# source_eagle.net
KiCad netlist of a schematic drawn in EAGLE
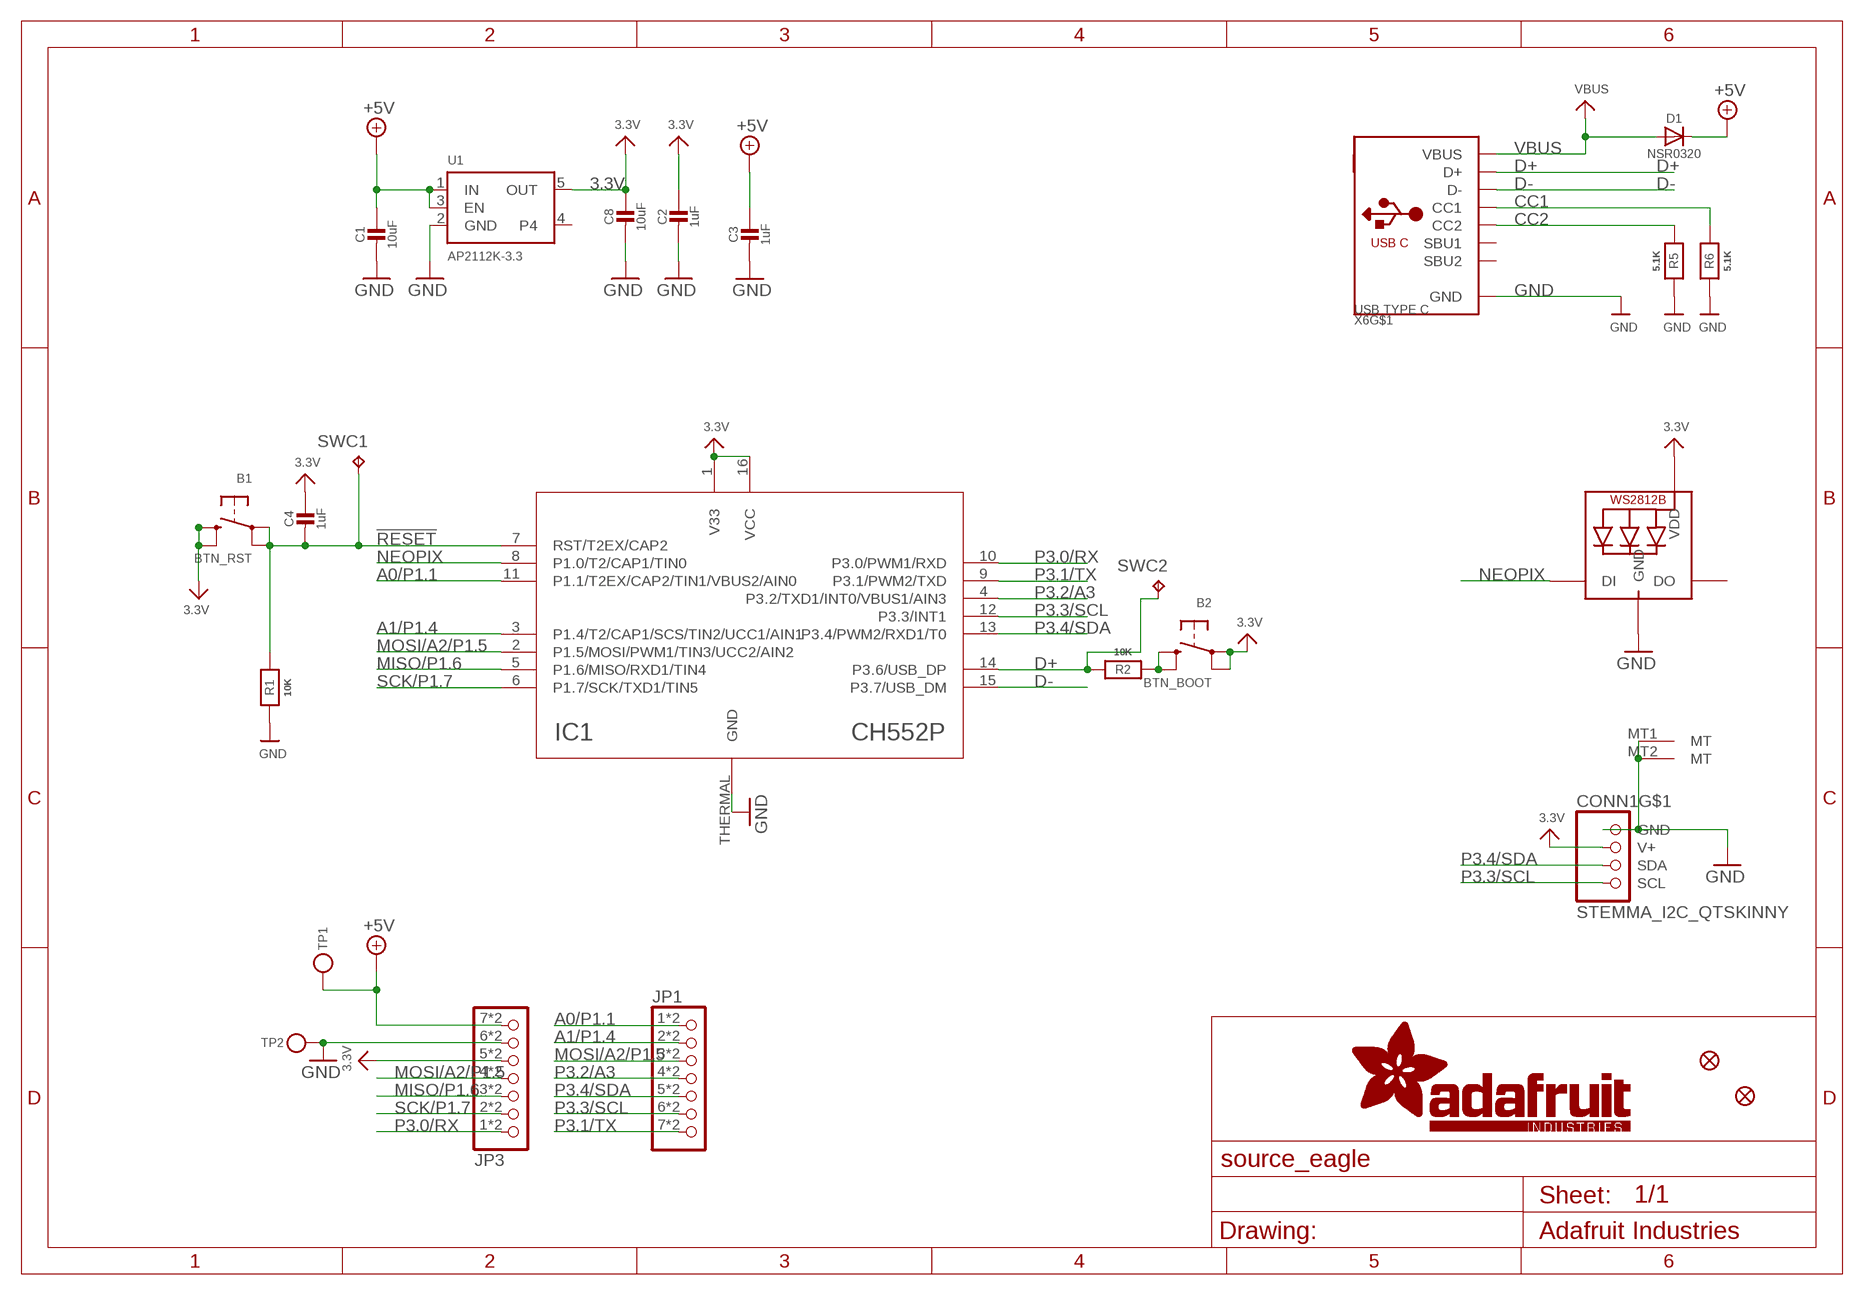
[diagram p0: schematic, sheet 1]

(export (version "E")
  (design (tool "Eeschema 10.0.6"))
  (components
    (comp (ref "B1")
      (value "BTN_RST")
      (footprint "eagle-import:BTN_RKB2_4.6X2.8")
      (libsource (lib "eagle-import") (part "SWITCH_TACT_SMT_RKB2"))
    )
    (comp (ref "B2")
      (value "BTN_BOOT")
      (footprint "eagle-import:BTN_RKB2_4.6X2.8")
      (libsource (lib "eagle-import") (part "SWITCH_TACT_SMT_RKB2"))
    )
    (comp (ref "C1")
      (value "10uF")
      (footprint "eagle-import:_0805MP")
      (libsource (lib "eagle-import") (part "CAP_CERAMIC_0805MP"))
    )
    (comp (ref "C2")
      (value "1uF")
      (footprint "eagle-import:_0402NO")
      (libsource (lib "eagle-import") (part "CAP_CERAMIC_0402NO"))
    )
    (comp (ref "C3")
      (value "1uF")
      (footprint "eagle-import:_0402NO")
      (libsource (lib "eagle-import") (part "CAP_CERAMIC_0402NO"))
    )
    (comp (ref "C4")
      (value "1uF")
      (footprint "eagle-import:_0402NO")
      (libsource (lib "eagle-import") (part "CAP_CERAMIC_0402NO"))
    )
    (comp (ref "C8")
      (value "10uF")
      (footprint "eagle-import:_0805MP")
      (libsource (lib "eagle-import") (part "CAP_CERAMIC_0805MP"))
    )
    (comp (ref "CONN1")
      (value "STEMMA_I2C_QTSKINNY")
      (footprint "eagle-import:JST_SH4_SKINNY")
      (libsource (lib "eagle-import") (part "STEMMA_I2C_QTSKINNY"))
    )
    (comp (ref "D1")
      (value "NSR0320")
      (footprint "eagle-import:SOD-323_MINI")
      (libsource (lib "eagle-import") (part "DIODE_SOD323MINI"))
    )
    (comp (ref "IC1")
      (value "CH552PP")
      (footprint "eagle-import:QFN16_3MM")
      (libsource (lib "eagle-import") (part "CH552PP"))
    )
    (comp (ref "JP1")
      (value "HEADER-1X7_CASTEL")
      (footprint "eagle-import:1X07_CASTEL")
      (libsource (lib "eagle-import") (part "HEADER-1X7_CASTEL"))
    )
    (comp (ref "JP3")
      (value "HEADER-1X7_CASTEL")
      (footprint "eagle-import:1X07_CASTEL")
      (libsource (lib "eagle-import") (part "HEADER-1X7_CASTEL"))
    )
    (comp (ref "LED1")
      (value "WS2812B_SK6805_1515")
      (footprint "eagle-import:SK6805_1515")
      (libsource (lib "eagle-import") (part "WS2812B_SK6805_1515"))
    )
    (comp (ref "R1")
      (value "10K")
      (footprint "eagle-import:_0402NO")
      (libsource (lib "eagle-import") (part "RESISTOR_0402NO"))
    )
    (comp (ref "R2")
      (value "10K")
      (footprint "eagle-import:_0402NO")
      (libsource (lib "eagle-import") (part "RESISTOR_0402NO"))
    )
    (comp (ref "R5")
      (value "5.1K")
      (footprint "eagle-import:_0402NO")
      (libsource (lib "eagle-import") (part "RESISTOR_0402NO"))
    )
    (comp (ref "R6")
      (value "5.1K")
      (footprint "eagle-import:_0402NO")
      (libsource (lib "eagle-import") (part "RESISTOR_0402NO"))
    )
    (comp (ref "SWC1")
      (value "TPB1,27")
      (footprint "eagle-import:B1,27")
      (libsource (lib "eagle-import") (part "TPB1,27"))
    )
    (comp (ref "SWC2")
      (value "TPTP15R")
      (footprint "eagle-import:TP15R")
      (libsource (lib "eagle-import") (part "TPTP15R"))
    )
    (comp (ref "TP1")
      (value "TESTPOINT_PLUS13")
      (footprint "eagle-import:TESTPOINT_PLUS_1X3MM")
      (libsource (lib "eagle-import") (part "TESTPOINT_PLUS13"))
    )
    (comp (ref "TP2")
      (value "TESTPOINT_MINUS")
      (footprint "eagle-import:TESTPOINT_MINUS_1X3MM")
      (libsource (lib "eagle-import") (part "TESTPOINT_MINUS"))
    )
    (comp (ref "U$6")
      (value "FIDUCIAL_1MM")
      (footprint "eagle-import:FIDUCIAL_1MM")
      (libsource (lib "eagle-import") (part "FIDUCIAL_1MM"))
    )
    (comp (ref "U$8")
      (value "FIDUCIAL_1MM")
      (footprint "eagle-import:FIDUCIAL_1MM")
      (libsource (lib "eagle-import") (part "FIDUCIAL_1MM"))
    )
    (comp (ref "U1")
      (value "AP2112K-3.3")
      (footprint "eagle-import:SOT23-5")
      (libsource (lib "eagle-import") (part "VREG_SOT23-5"))
    )
    (comp (ref "X6")
      (value "USB TYPE C")
      (footprint "eagle-import:USB_C_CUSB31-CFM2AX-01-X")
      (libsource (lib "eagle-import") (part "USB_C"))
    )
  )
  (nets
    (net (code "1") (name "+5V") (class "Default")
      (node (ref "C1") (pin "1") (pinfunction "1_1") (pintype "passive"))
      (node (ref "C3") (pin "1") (pinfunction "1_1") (pintype "passive"))
      (node (ref "D1") (pin "C") (pinfunction "C_C") (pintype "passive"))
      (node (ref "JP3") (pin "7") (pinfunction "7_7") (pintype "passive"))
      (node (ref "JP3") (pin "7C") (pinfunction "7_7C") (pintype "passive"))
      (node (ref "TP1") (pin "P$1") (pinfunction "P$1_P$1") (pintype "bidirectional"))
      (node (ref "U1") (pin "1") (pinfunction "IN_1") (pintype "power_in"))
      (node (ref "U1") (pin "3") (pinfunction "EN_3") (pintype "input"))
    )
    (net (code "2") (name "/A0{slash}P1.1") (class "Default")
      (node (ref "IC1") (pin "11") (pinfunction "P1.1/T2EX/CAP2/TIN1/VBUS2/AIN0_11") (pintype "bidirectional"))
      (node (ref "JP1") (pin "1") (pinfunction "1_1") (pintype "passive"))
      (node (ref "JP1") (pin "1C") (pinfunction "1_1C") (pintype "passive"))
    )
    (net (code "3") (name "/A1{slash}P1.4") (class "Default")
      (node (ref "IC1") (pin "3") (pinfunction "P1.4/T2/CAP1/SCS/TIN2/UCC1/AIN1_3") (pintype "bidirectional"))
      (node (ref "JP1") (pin "2") (pinfunction "2_2") (pintype "passive"))
      (node (ref "JP1") (pin "2C") (pinfunction "2_2C") (pintype "passive"))
    )
    (net (code "4") (name "/CC1") (class "Default")
      (node (ref "R6") (pin "2") (pinfunction "2_2") (pintype "passive"))
      (node (ref "X6") (pin "A5") (pinfunction "CC1_A5") (pintype "bidirectional"))
    )
    (net (code "5") (name "/CC2") (class "Default")
      (node (ref "R5") (pin "2") (pinfunction "2_2") (pintype "passive"))
      (node (ref "X6") (pin "B5") (pinfunction "CC2_B5") (pintype "bidirectional"))
    )
    (net (code "6") (name "/D+") (class "Default")
      (node (ref "IC1") (pin "14") (pinfunction "P3.6/USB_DP_14") (pintype "bidirectional"))
      (node (ref "R2") (pin "2") (pinfunction "2_2") (pintype "passive"))
      (node (ref "SWC2") (pin "TP") (pinfunction "TP_TP") (pintype "input"))
      (node (ref "X6") (pin "A6") (pinfunction "D+_A6") (pintype "bidirectional"))
      (node (ref "X6") (pin "B6") (pinfunction "D+_B6") (pintype "bidirectional"))
    )
    (net (code "7") (name "/D-") (class "Default")
      (node (ref "IC1") (pin "15") (pinfunction "P3.7/USB_DM_15") (pintype "bidirectional"))
      (node (ref "X6") (pin "A7") (pinfunction "D-_A7") (pintype "bidirectional"))
      (node (ref "X6") (pin "B7") (pinfunction "D-_B7") (pintype "bidirectional"))
    )
    (net (code "8") (name "/MISO{slash}P1.6") (class "Default")
      (node (ref "IC1") (pin "5") (pinfunction "P1.6/MISO/RXD1/TIN4_5") (pintype "bidirectional"))
      (node (ref "JP3") (pin "3") (pinfunction "3_3") (pintype "passive"))
      (node (ref "JP3") (pin "3C") (pinfunction "3_3C") (pintype "passive"))
    )
    (net (code "9") (name "/MOSI{slash}A2{slash}P1.5") (class "Default")
      (node (ref "IC1") (pin "2") (pinfunction "P1.5/MOSI/PWM1/TIN3/UCC2/AIN2_2") (pintype "bidirectional"))
      (node (ref "JP1") (pin "3") (pinfunction "3_3") (pintype "passive"))
      (node (ref "JP1") (pin "3C") (pinfunction "3_3C") (pintype "passive"))
      (node (ref "JP3") (pin "4") (pinfunction "4_4") (pintype "passive"))
      (node (ref "JP3") (pin "4C") (pinfunction "4_4C") (pintype "passive"))
    )
    (net (code "10") (name "/NEOPIX") (class "Default")
      (node (ref "IC1") (pin "8") (pinfunction "P1.0/T2/CAP1/TIN0_8") (pintype "bidirectional"))
      (node (ref "LED1") (pin "1") (pinfunction "DI_1") (pintype "input"))
    )
    (net (code "11") (name "/P3.0{slash}RX") (class "Default")
      (node (ref "IC1") (pin "10") (pinfunction "P3.0/PWM1/RXD_10") (pintype "bidirectional"))
      (node (ref "JP3") (pin "1") (pinfunction "1_1") (pintype "passive"))
      (node (ref "JP3") (pin "1C") (pinfunction "1_1C") (pintype "passive"))
    )
    (net (code "12") (name "/P3.1{slash}TX") (class "Default")
      (node (ref "IC1") (pin "9") (pinfunction "P3.1/PWM2/TXD_9") (pintype "bidirectional"))
      (node (ref "JP1") (pin "7") (pinfunction "7_7") (pintype "passive"))
      (node (ref "JP1") (pin "7C") (pinfunction "7_7C") (pintype "passive"))
    )
    (net (code "13") (name "/P3.2{slash}A3") (class "Default")
      (node (ref "IC1") (pin "4") (pinfunction "P3.2/TXD1/INT0/VBUS1/AIN3_4") (pintype "bidirectional"))
      (node (ref "JP1") (pin "4") (pinfunction "4_4") (pintype "passive"))
      (node (ref "JP1") (pin "4C") (pinfunction "4_4C") (pintype "passive"))
    )
    (net (code "14") (name "/P3.3{slash}SCL") (class "Default")
      (node (ref "CONN1") (pin "4") (pinfunction "SCL_4") (pintype "passive"))
      (node (ref "IC1") (pin "12") (pinfunction "P3.3/INT1_12") (pintype "bidirectional"))
      (node (ref "JP1") (pin "6") (pinfunction "6_6") (pintype "passive"))
      (node (ref "JP1") (pin "6C") (pinfunction "6_6C") (pintype "passive"))
    )
    (net (code "15") (name "/P3.4{slash}SDA") (class "Default")
      (node (ref "CONN1") (pin "3") (pinfunction "SDA_3") (pintype "passive"))
      (node (ref "IC1") (pin "13") (pinfunction "P3.4/PWM2/RXD1/T0_13") (pintype "bidirectional"))
      (node (ref "JP1") (pin "5") (pinfunction "5_5") (pintype "passive"))
      (node (ref "JP1") (pin "5C") (pinfunction "5_5C") (pintype "passive"))
    )
    (net (code "16") (name "/SCK{slash}P1.7") (class "Default")
      (node (ref "IC1") (pin "6") (pinfunction "P1.7/SCK/TXD1/TIN5_6") (pintype "bidirectional"))
      (node (ref "JP3") (pin "2") (pinfunction "2_2") (pintype "passive"))
      (node (ref "JP3") (pin "2C") (pinfunction "2_2C") (pintype "passive"))
    )
    (net (code "17") (name "/~{RESET}") (class "Default")
      (node (ref "B1") (pin "A") (pinfunction "P_A") (pintype "passive"))
      (node (ref "B1") (pin "A'") (pinfunction "P1_A'") (pintype "passive"))
      (node (ref "C4") (pin "2") (pinfunction "2_2") (pintype "passive"))
      (node (ref "IC1") (pin "7") (pinfunction "RST/T2EX/CAP2_7") (pintype "bidirectional"))
      (node (ref "R1") (pin "2") (pinfunction "2_2") (pintype "passive"))
      (node (ref "SWC1") (pin "TP") (pinfunction "TP_TP") (pintype "input"))
    )
    (net (code "18") (name "3.3V") (class "Default")
      (node (ref "B1") (pin "B") (pinfunction "S_B") (pintype "passive"))
      (node (ref "B1") (pin "B'") (pinfunction "S1_B'") (pintype "passive"))
      (node (ref "B2") (pin "A") (pinfunction "P_A") (pintype "passive"))
      (node (ref "B2") (pin "A'") (pinfunction "P1_A'") (pintype "passive"))
      (node (ref "C2") (pin "1") (pinfunction "1_1") (pintype "passive"))
      (node (ref "C4") (pin "1") (pinfunction "1_1") (pintype "passive"))
      (node (ref "C8") (pin "1") (pinfunction "1_1") (pintype "passive"))
      (node (ref "CONN1") (pin "2") (pinfunction "V+_2") (pintype "passive"))
      (node (ref "IC1") (pin "1") (pinfunction "V33_1") (pintype "power_in"))
      (node (ref "IC1") (pin "16") (pinfunction "VCC_16") (pintype "power_in"))
      (node (ref "JP3") (pin "5") (pinfunction "5_5") (pintype "passive"))
      (node (ref "JP3") (pin "5C") (pinfunction "5_5C") (pintype "passive"))
      (node (ref "LED1") (pin "2") (pinfunction "VDD_2") (pintype "power_in"))
      (node (ref "U1") (pin "5") (pinfunction "OUT_5") (pintype "power_in"))
    )
    (net (code "19") (name "GND") (class "Default")
      (node (ref "C1") (pin "2") (pinfunction "2_2") (pintype "passive"))
      (node (ref "C2") (pin "2") (pinfunction "2_2") (pintype "passive"))
      (node (ref "C3") (pin "2") (pinfunction "2_2") (pintype "passive"))
      (node (ref "C8") (pin "2") (pinfunction "2_2") (pintype "passive"))
      (node (ref "CONN1") (pin "1") (pinfunction "GND_1") (pintype "passive"))
      (node (ref "CONN1") (pin "MT1") (pinfunction "MT_MT1") (pintype "bidirectional"))
      (node (ref "CONN1") (pin "MT2") (pinfunction "MT_MT2") (pintype "bidirectional"))
      (node (ref "IC1") (pin "THERMAL") (pinfunction "GND_THERMAL") (pintype "power_in"))
      (node (ref "JP3") (pin "6") (pinfunction "6_6") (pintype "passive"))
      (node (ref "JP3") (pin "6C") (pinfunction "6_6C") (pintype "passive"))
      (node (ref "LED1") (pin "4") (pinfunction "GND_4") (pintype "power_in"))
      (node (ref "R1") (pin "1") (pinfunction "1_1") (pintype "passive"))
      (node (ref "R5") (pin "1") (pinfunction "1_1") (pintype "passive"))
      (node (ref "R6") (pin "1") (pinfunction "1_1") (pintype "passive"))
      (node (ref "TP2") (pin "P$1") (pinfunction "P$1_P$1") (pintype "bidirectional"))
      (node (ref "U1") (pin "2") (pinfunction "GND_2") (pintype "power_in"))
      (node (ref "X6") (pin "A1B12") (pinfunction "GND_A1B12") (pintype "power_in"))
      (node (ref "X6") (pin "B1A12") (pinfunction "GND_B1A12") (pintype "power_in"))
    )
    (net (code "20") (name "Net-(B2-S)") (class "Default")
      (node (ref "B2") (pin "B") (pinfunction "S_B") (pintype "passive"))
      (node (ref "B2") (pin "B'") (pinfunction "S1_B'") (pintype "passive"))
      (node (ref "R2") (pin "1") (pinfunction "1_1") (pintype "passive"))
    )
    (net (code "21") (name "VBUS") (class "Default")
      (node (ref "D1") (pin "A") (pinfunction "A_A") (pintype "passive"))
      (node (ref "X6") (pin "A4B9") (pinfunction "VBUS_A4B9") (pintype "power_in"))
      (node (ref "X6") (pin "B4A9") (pinfunction "VBUS_B4A9") (pintype "power_in"))
    )
    (net (code "22") (name "unconnected-(LED1-DO-Pad3)") (class "Default")
      (node (ref "LED1") (pin "3") (pinfunction "DO_3") (pintype "output"))
    )
    (net (code "23") (name "unconnected-(U1-P4-Pad4)") (class "Default")
      (node (ref "U1") (pin "4") (pinfunction "P4_4") (pintype "bidirectional"))
    )
    (net (code "24") (name "unconnected-(X6A-SBU1-PadA8)") (class "Default")
      (node (ref "X6") (pin "A8") (pinfunction "SBU1_A8") (pintype "bidirectional"))
    )
    (net (code "25") (name "unconnected-(X6A-SBU2-PadB8)") (class "Default")
      (node (ref "X6") (pin "B8") (pinfunction "SBU2_B8") (pintype "bidirectional"))
    )
  )
)
